# PSU_Power_Supply_Unit.net
KiCad netlist of a schematic drawn in Altium Designer
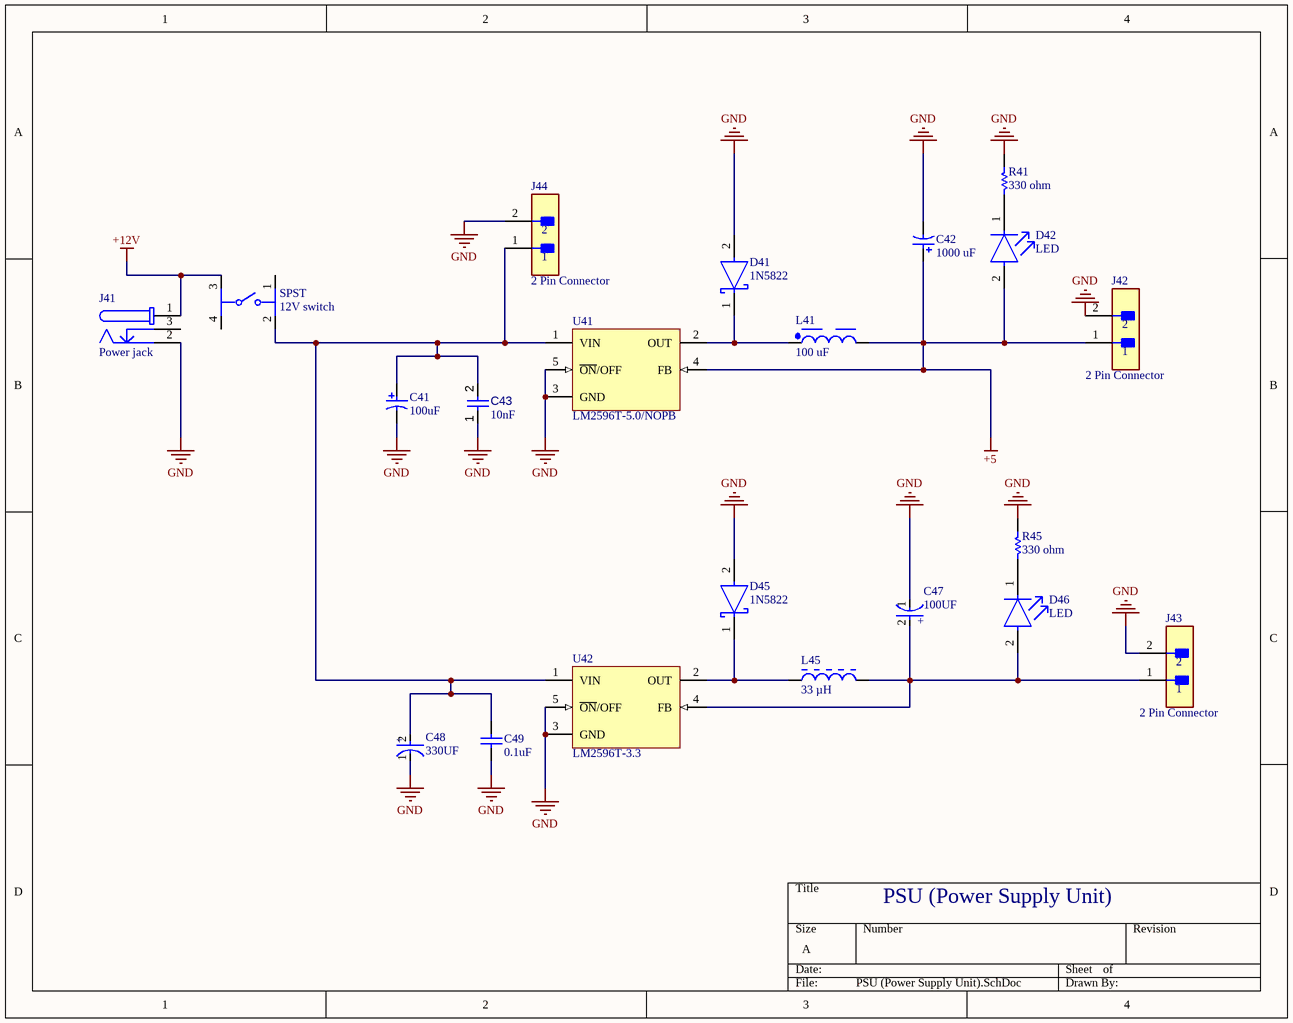
[diagram p0: PSU (Power Supply Unit).SchDoc]

(export (version "E")
  (design (tool "Eeschema 10.0.6"))
  (components
    (comp (ref "C41")
      (value "100uF")
      (footprint "PNSC-FK-V-D8_V")
      (fields (field (name "MANUFACTURER") "Panasonic"))
      (libsource (lib "Altium Content Vault") (part "CAP-P-2"))
    )
    (comp (ref "C42")
      (value "1000 uF")
      (footprint "PNSC-FR-A-8X20-2_V")
      (fields
        (field (name "PARTNUMBER") "EEU-FR1C102L")
        (field (name "TOLERANCE") "+/- 20%")
        (field (name "MANUFACTURER") "Panasonic")
      )
      (libsource (lib "Altium Content Vault") (part "PNSC-CAP-P-2"))
    )
    (comp (ref "C43")
      (value "10nF")
      (footprint "CAPC0402(1005)60_L")
      (description "Chip Capacitor, 10nF +/-20%, 50V, 0402, Thickness 0.6 mm")
      (fields (field (name "TOLERANCE") "5%") (field (name "Comment") "Capacitor 10nF +/-20% 50V 0402"))
      (libsource (lib "University of Salford") (part "CAP-NP-2"))
    )
    (comp (ref "C47")
      (value "100UF")
      (footprint "FP-SC-MFG")
      (description "CAP ALUM 100UF 20% 10V SMD")
      (fields (field (name "TOLERANCE") "20%"))
      (libsource (lib "Altium Content Vault") (part "a00bbbee19879c290e62620ae7e47b1"))
    )
    (comp (ref "C48")
      (value "330UF")
      (footprint "FP-FTG-MFG")
      (description "CAP ALUM 330UF 20% 50V SMD")
      (fields (field (name "TOLERANCE") "20%") (field (name "VOLTAGE") "50V"))
      (libsource (lib "Altium Content Vault") (part "203bc49f2ac43e59fd269a8c329ed05"))
    )
    (comp (ref "C49")
      (value "0.1uF")
      (footprint "CAPC1005X55X30LL05T10")
      (fields (field (name "MANUFACTURER") "Kemet") (field (name "PART NUMBER") "C0402C104K4RACTU"))
      (libsource (lib "Altium Content Vault") (part "CAP"))
    )
    (comp (ref "D41")
      (value "1N5822")
      (footprint "FP-DO-201AD-MFG")
      (description "DIODE SCHOTTKY 40V 3A DO201AD")
      (fields
        (field (name "OCTOPART") "https://octopart.com/1n5822-stmicroelectronics-323225")
        (field (name "MANUFACTURER") "STMicroelectronics")
      )
      (libsource (lib "Altium Content Vault") (part "1d6ec82d83fb6aee721767c19dac4b9"))
    )
    (comp (ref "D42")
      (value "LED")
      (footprint "FP-LTST-S270KRKT-MFG")
      (description "LED RED CLEAR CHIP SMD R/A")
      (libsource (lib "Altium Content Vault") (part "8706943c75ba83719d021d2fdc84c58"))
    )
    (comp (ref "D45")
      (value "1N5822")
      (footprint "FP-DO-201AD-MFG")
      (description "DIODE SCHOTTKY 40V 3A DO201AD")
      (fields
        (field (name "OCTOPART") "https://octopart.com/1n5822-stmicroelectronics-323225")
        (field (name "MANUFACTURER") "STMicroelectronics")
      )
      (libsource (lib "Altium Content Vault") (part "1d6ec82d83fb6aee721767c19dac4b9"))
    )
    (comp (ref "D46")
      (value "LED")
      (footprint "FP-LTST-S270KRKT-MFG")
      (description "LED RED CLEAR CHIP SMD R/A")
      (libsource (lib "Altium Content Vault") (part "8706943c75ba83719d021d2fdc84c58"))
    )
    (comp (ref "J41")
      (value "Power jack")
      (footprint "694106301002")
      (libsource (lib "Altium Content Vault") (part "DC Power Jack"))
    )
    (comp (ref "J42")
      (value "2 Pin Connector")
      (footprint "FP-53048-0210-MFG")
      (description "CONN HEADER R/A 2POS 1.25MM")
      (libsource (lib "Altium Content Vault") (part "88c1139f9d239099ffebecbe3f7647a"))
    )
    (comp (ref "J43")
      (value "2 Pin Connector")
      (footprint "FP-53048-0210-MFG")
      (description "CONN HEADER R/A 2POS 1.25MM")
      (libsource (lib "Altium Content Vault") (part "88c1139f9d239099ffebecbe3f7647a"))
    )
    (comp (ref "J44")
      (value "2 Pin Connector")
      (footprint "FP-53048-0210-MFG")
      (description "CONN HEADER R/A 2POS 1.25MM")
      (libsource (lib "Altium Content Vault") (part "88c1139f9d239099ffebecbe3f7647a"))
    )
    (comp (ref "L41")
      (value "100 uF")
      (footprint "WE-PD2_5848")
      (libsource (lib "Altium Content Vault") (part "Inductor - 2"))
    )
    (comp (ref "L45")
      (value "33 µH")
      (footprint "BOUR-SRN3015-2_V")
      (fields (field (name "PARTNUMBER") "SRN3015-330M") (field (name "MANUFACTURER") "Bourns"))
      (libsource (lib "Altium Content Vault") (part "BOUR-IND-2A"))
    )
    (comp (ref "R41")
      (value "330 ohm")
      (footprint "RESC1608X55X30LL15T15")
      (description "Chip Resistor, 330 Ohm, +/- 1%, 0.1 W, -55 to 155 degC, 0603 (1608 Metric), RoHS, Tape and Reel")
      (libsource (lib "Altium Content Vault") (part "RES-2"))
    )
    (comp (ref "R45")
      (value "330 ohm")
      (footprint "RESC1608X55X30LL15T15")
      (description "Chip Resistor, 330 Ohm, +/- 1%, 0.1 W, -55 to 155 degC, 0603 (1608 Metric), RoHS, Tape and Reel")
      (libsource (lib "Altium Content Vault") (part "RES-2"))
    )
    (comp (ref "SPST")
      (value "12V switch")
      (footprint "FP-PTS645SM43SMTR92LFS-MFG")
      (description "SWITCH TACTILE SPST-NO 0.05A 12V")
      (libsource (lib "Altium Content Vault") (part "1adf0dd01260c80cf25a44bfd6b99ba"))
    )
    (comp (ref "U41")
      (value "LM2596T-5.0/NOPB")
      (footprint "NDH0005A")
      (description "SIMPLE SWITCHER® Power Converter 150 KHz 3A Step-Down Voltage Regulator, 5-pin TO-220, Pb-Free")
      (fields (field (name "MANUFACTURER") "Texas Instruments"))
      (libsource (lib "Altium Content Vault") (part "PM-REG-LM2575HVT-12"))
    )
    (comp (ref "U42")
      (value "LM2596T-3.3")
      (footprint "T05D")
      (description "SIMPLE SWITCHER® Power Converter 150 KHz 3A Step-Down Voltage Regulator, 5-pin TO-220")
      (fields (field (name "MANUFACTURER") "National Semiconductor"))
      (libsource (lib "Altium Content Vault") (part "PM-REG-LM2575HVT-12"))
    )
  )
  (nets
    (net (code "1") (name "+5") (class "Default")
      (node (ref "C42") (pin "1") (pinfunction "1_1") (pintype "passive"))
      (node (ref "D42") (pin "2") (pinfunction "A_2") (pintype "passive"))
      (node (ref "J42") (pin "1") (pinfunction "1_1") (pintype "passive"))
      (node (ref "L41") (pin "2") (pinfunction "2_2") (pintype "passive"))
      (node (ref "U41") (pin "4") (pinfunction "FB_4") (pintype "input"))
    )
    (net (code "2") (name "+12V") (class "Default")
      (node (ref "J41") (pin "1") (pinfunction "1_1") (pintype "passive"))
      (node (ref "SPST") (pin "3") (pinfunction "3_3") (pintype "passive"))
    )
    (net (code "3") (name "GND") (class "Default")
      (node (ref "C41") (pin "2") (pinfunction "2_2") (pintype "passive"))
      (node (ref "C42") (pin "2") (pinfunction "2_2") (pintype "passive"))
      (node (ref "C43") (pin "1") (pinfunction "1_1") (pintype "passive"))
      (node (ref "C47") (pin "1") (pinfunction "C_1") (pintype "passive"))
      (node (ref "C48") (pin "1") (pinfunction "C_1") (pintype "passive"))
      (node (ref "C49") (pin "1") (pinfunction "1_1") (pintype "passive"))
      (node (ref "D41") (pin "2") (pinfunction "A_2") (pintype "passive"))
      (node (ref "D45") (pin "2") (pinfunction "A_2") (pintype "passive"))
      (node (ref "J41") (pin "2") (pinfunction "2_2") (pintype "passive"))
      (node (ref "J42") (pin "2") (pinfunction "2_2") (pintype "passive"))
      (node (ref "J43") (pin "2") (pinfunction "2_2") (pintype "passive"))
      (node (ref "J44") (pin "2") (pinfunction "2_2") (pintype "passive"))
      (node (ref "R41") (pin "1") (pinfunction "1_1") (pintype "passive"))
      (node (ref "R45") (pin "1") (pinfunction "1_1") (pintype "passive"))
      (node (ref "U41") (pin "3") (pinfunction "GND_3") (pintype "power_in"))
      (node (ref "U41") (pin "5") (pinfunction "~{ON}/OFF_5") (pintype "input"))
      (node (ref "U42") (pin "3") (pinfunction "GND_3") (pintype "power_in"))
      (node (ref "U42") (pin "5") (pinfunction "~{ON}/OFF_5") (pintype "input"))
    )
    (net (code "4") (name "Net-(C47-A)") (class "Default")
      (node (ref "C47") (pin "2") (pinfunction "A_2") (pintype "passive"))
      (node (ref "D46") (pin "2") (pinfunction "A_2") (pintype "passive"))
      (node (ref "J43") (pin "1") (pinfunction "1_1") (pintype "passive"))
      (node (ref "L45") (pin "2") (pinfunction "2_2") (pintype "passive"))
      (node (ref "U42") (pin "4") (pinfunction "FB_4") (pintype "input"))
    )
    (net (code "5") (name "Net-(C48-A)") (class "Default")
      (node (ref "C41") (pin "1") (pinfunction "1_1") (pintype "passive"))
      (node (ref "C43") (pin "2") (pinfunction "2_2") (pintype "passive"))
      (node (ref "C48") (pin "2") (pinfunction "A_2") (pintype "passive"))
      (node (ref "C49") (pin "2") (pinfunction "2_2") (pintype "passive"))
      (node (ref "J44") (pin "1") (pinfunction "1_1") (pintype "passive"))
      (node (ref "SPST") (pin "2") (pinfunction "2_2") (pintype "passive"))
      (node (ref "U41") (pin "1") (pinfunction "VIN_1") (pintype "power_in"))
      (node (ref "U42") (pin "1") (pinfunction "VIN_1") (pintype "power_in"))
    )
    (net (code "6") (name "Net-(D41-C)") (class "Default")
      (node (ref "D41") (pin "1") (pinfunction "C_1") (pintype "passive"))
      (node (ref "L41") (pin "1") (pinfunction "1_1") (pintype "passive"))
      (node (ref "U41") (pin "2") (pinfunction "OUT_2") (pintype "power_in"))
    )
    (net (code "7") (name "Net-(D42-C)") (class "Default")
      (node (ref "D42") (pin "1") (pinfunction "C_1") (pintype "passive"))
      (node (ref "R41") (pin "2") (pinfunction "2_2") (pintype "passive"))
    )
    (net (code "8") (name "Net-(D45-C)") (class "Default")
      (node (ref "D45") (pin "1") (pinfunction "C_1") (pintype "passive"))
      (node (ref "L45") (pin "1") (pinfunction "1_1") (pintype "passive"))
      (node (ref "U42") (pin "2") (pinfunction "OUT_2") (pintype "power_in"))
    )
    (net (code "9") (name "Net-(D46-C)") (class "Default")
      (node (ref "D46") (pin "1") (pinfunction "C_1") (pintype "passive"))
      (node (ref "R45") (pin "2") (pinfunction "2_2") (pintype "passive"))
    )
    (net (code "10") (name "unconnected-(J41-Pad3)") (class "Default")
      (node (ref "J41") (pin "3") (pinfunction "3_3") (pintype "passive"))
    )
    (net (code "11") (name "unconnected-(SPST-Pad1)") (class "Default")
      (node (ref "SPST") (pin "1") (pinfunction "1_1") (pintype "passive"))
    )
    (net (code "12") (name "unconnected-(SPST-Pad4)") (class "Default")
      (node (ref "SPST") (pin "4") (pinfunction "4_4") (pintype "passive"))
    )
  )
)
